# Microcontroller.net
KiCad netlist of a schematic drawn in Altium Designer
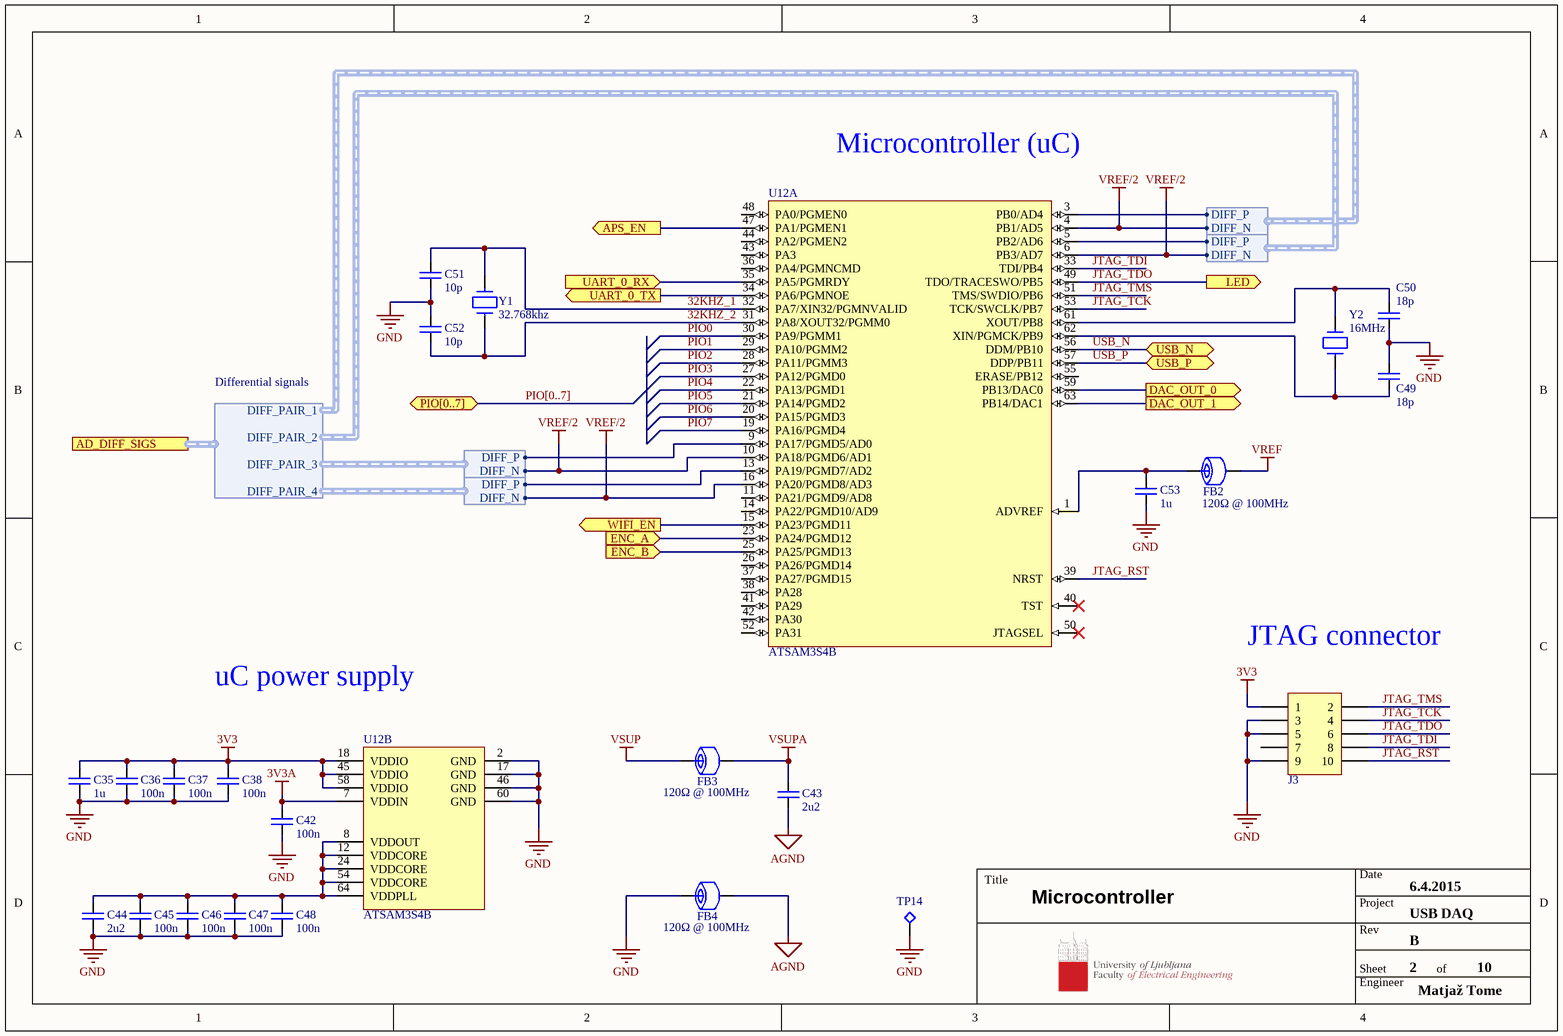
[diagram p0: Microcontroller.SchDoc]

(export (version "E")
  (design (tool "Eeschema 10.0.6"))
  (components
    (comp (ref "C35")
      (value "1u")
      (footprint "C_0603")
      (description "Generic capacitor")
      (fields (field (name "Comment") "comment"))
      (libsource (lib "DAQ") (part "Capacitor"))
    )
    (comp (ref "C36")
      (value "100n")
      (footprint "C_0603")
      (description "Generic capacitor")
      (fields (field (name "Comment") "comment"))
      (libsource (lib "DAQ") (part "Capacitor"))
    )
    (comp (ref "C37")
      (value "100n")
      (footprint "C_0603")
      (description "Generic capacitor")
      (fields (field (name "Comment") "comment"))
      (libsource (lib "DAQ") (part "Capacitor"))
    )
    (comp (ref "C38")
      (value "100n")
      (footprint "C_0603")
      (description "Generic capacitor")
      (fields (field (name "Comment") "comment"))
      (libsource (lib "DAQ") (part "Capacitor"))
    )
    (comp (ref "C42")
      (value "100n")
      (footprint "C_0603")
      (description "Generic capacitor")
      (fields (field (name "Comment") "comment"))
      (libsource (lib "DAQ") (part "Capacitor"))
    )
    (comp (ref "C43")
      (value "2u2")
      (footprint "C_0603")
      (description "Generic capacitor")
      (fields (field (name "Comment") "comment"))
      (libsource (lib "DAQ") (part "Capacitor"))
    )
    (comp (ref "C44")
      (value "2u2")
      (footprint "C_0603")
      (description "Generic capacitor")
      (fields (field (name "Comment") "comment"))
      (libsource (lib "DAQ") (part "Capacitor"))
    )
    (comp (ref "C45")
      (value "100n")
      (footprint "C_0603")
      (description "Generic capacitor")
      (fields (field (name "Comment") "comment"))
      (libsource (lib "DAQ") (part "Capacitor"))
    )
    (comp (ref "C46")
      (value "100n")
      (footprint "C_0603")
      (description "Generic capacitor")
      (fields (field (name "Comment") "comment"))
      (libsource (lib "DAQ") (part "Capacitor"))
    )
    (comp (ref "C47")
      (value "100n")
      (footprint "C_0603")
      (description "Generic capacitor")
      (fields (field (name "Comment") "comment"))
      (libsource (lib "DAQ") (part "Capacitor"))
    )
    (comp (ref "C48")
      (value "100n")
      (footprint "C_0603")
      (description "Generic capacitor")
      (fields (field (name "Comment") "comment"))
      (libsource (lib "DAQ") (part "Capacitor"))
    )
    (comp (ref "C49")
      (value "18p")
      (footprint "C_0603")
      (description "Generic capacitor")
      (fields (field (name "Comment") "comment"))
      (libsource (lib "DAQ") (part "Capacitor"))
    )
    (comp (ref "C50")
      (value "18p")
      (footprint "C_0603")
      (description "Generic capacitor")
      (fields (field (name "Comment") "comment"))
      (libsource (lib "DAQ") (part "Capacitor"))
    )
    (comp (ref "C51")
      (value "10p")
      (footprint "C_0603")
      (description "Generic capacitor")
      (fields (field (name "Comment") "comment"))
      (libsource (lib "DAQ") (part "Capacitor"))
    )
    (comp (ref "C52")
      (value "10p")
      (footprint "C_0603")
      (description "Generic capacitor")
      (fields (field (name "Comment") "comment"))
      (libsource (lib "DAQ") (part "Capacitor"))
    )
    (comp (ref "C53")
      (value "1u")
      (footprint "C_0603")
      (description "Generic capacitor")
      (fields (field (name "Comment") "comment"))
      (libsource (lib "DAQ") (part "Capacitor"))
    )
    (comp (ref "FB2")
      (value "120Ω @ 100MHz")
      (footprint "SMD_0805")
      (description "Ferrite Bead, 0805 [2012 Metric], 120 ohm, 800 mA, BLM21A Series, 0.15 ohm, ± 25%")
      (fields (field (name "MANUFACTURER") "Murata"))
      (libsource (lib "DAQ") (part "BLM21AG121SN1D"))
    )
    (comp (ref "FB3")
      (value "120Ω @ 100MHz")
      (footprint "SMD_0805")
      (description "Ferrite Bead, 0805 [2012 Metric], 120 ohm, 800 mA, BLM21A Series, 0.15 ohm, ± 25%")
      (fields (field (name "MANUFACTURER") "Murata"))
      (libsource (lib "DAQ") (part "BLM21AG121SN1D"))
    )
    (comp (ref "FB4")
      (value "120Ω @ 100MHz")
      (footprint "SMD_0805")
      (description "Ferrite Bead, 0805 [2012 Metric], 120 ohm, 800 mA, BLM21A Series, 0.15 ohm, ± 25%")
      (fields (field (name "MANUFACTURER") "Murata"))
      (libsource (lib "DAQ") (part "BLM21AG121SN1D"))
    )
    (comp (ref "J3")
      (value "M50-3600542")
      (footprint "HEADER_2X05_1.27mm")
      (description "Pin Header, Board-to-Board, 1.27 mm, 2 Rows, 10 Contacts, Surface Mount, Archer M50 Series")
      (fields (field (name "MANUFACTURER") "Harwin"))
      (libsource (lib "DAQ") (part "M50-3600542"))
    )
    (comp (ref "TP14")
      (value "testpoint")
      (footprint "TP1_FULL")
      (description "testpoint 1.5mm diameter no hole")
      (fields (field (name "PART NUMBER") "XXC0006"))
      (libsource (lib "DAQ") (part "Test Point"))
    )
    (comp (ref "U12")
      (value "ATSAM3S4B")
      (footprint "LQFP64")
      (description "Cortex M3 ARM microcontroller")
      (fields (field (name "PART NUMBER") "XAM0003") (field (name "MANUFACTURER") "Atmel"))
      (libsource (lib "DAQ") (part "ATSAM3SXB"))
    )
    (comp (ref "Y1")
      (value "32.768khz")
      (footprint "2X6_FLAT")
      (description "Crystal, 32.768 kHz, Cylinder Radial, 6.2mm x 2mm Dia, 12.5 pF, 20 ppm, R26 Series")
      (fields (field (name "PART NUMBER") "XCR0010") (field (name "MANUFACTURER") "RALTRON"))
      (libsource (lib "DAQ") (part "R26-32.768- 12.5"))
    )
    (comp (ref "Y2")
      (value "16MHz")
      (footprint "5X3.2")
      (description "Crystal, 16 MHz, SMD, 5mm x 3.2mm, 30 ppm, 18 pF, 30 ppm, 7A Series")
      (fields (field (name "MANUFACTURER") "TCX"))
      (libsource (lib "DAQ") (part "7A-16.000MAAJ-T"))
    )
  )
  (nets
    (net (code "5") (name "/32KHZ_1") (class "Default")
      (node (ref "C51") (pin "1") (pinfunction "1_1") (pintype "passive"))
      (node (ref "U12") (pin "32") (pinfunction "PA7/XIN32/PGMNVALID_32") (pintype "bidirectional"))
      (node (ref "Y1") (pin "2") (pinfunction "2_2") (pintype "passive"))
    )
    (net (code "6") (name "/32KHZ_2") (class "Default")
      (node (ref "C52") (pin "1") (pinfunction "1_1") (pintype "passive"))
      (node (ref "U12") (pin "31") (pinfunction "PA8/XOUT32/PGMM0_31") (pintype "bidirectional"))
      (node (ref "Y1") (pin "1") (pinfunction "1_1") (pintype "passive"))
    )
    (net (code "8") (name "/APS_EN") (class "Default")
      (node (ref "U12") (pin "47") (pinfunction "PA1/PGMEN1_47") (pintype "bidirectional"))
    )
    (net (code "9") (name "/DAC_OUT_0") (class "Default")
      (node (ref "U12") (pin "59") (pinfunction "PB13/DAC0_59") (pintype "bidirectional"))
    )
    (net (code "10") (name "/DAC_OUT_1") (class "Default")
      (node (ref "U12") (pin "63") (pinfunction "PB14/DAC1_63") (pintype "bidirectional"))
    )
    (net (code "11") (name "/ENC_A") (class "Default")
      (node (ref "U12") (pin "23") (pinfunction "PA24/PGMD12_23") (pintype "bidirectional"))
    )
    (net (code "12") (name "/ENC_B") (class "Default")
      (node (ref "U12") (pin "25") (pinfunction "PA25/PGMD13_25") (pintype "bidirectional"))
    )
    (net (code "13") (name "/JTAG_RST") (class "Default")
      (node (ref "J3") (pin "10") (pinfunction "10_10") (pintype "passive"))
      (node (ref "U12") (pin "39") (pinfunction "NRST_39") (pintype "bidirectional"))
    )
    (net (code "14") (name "/JTAG_TCK") (class "Default")
      (node (ref "J3") (pin "4") (pinfunction "4_4") (pintype "passive"))
      (node (ref "U12") (pin "53") (pinfunction "TCK/SWCLK/PB7_53") (pintype "bidirectional"))
    )
    (net (code "15") (name "/JTAG_TDI") (class "Default")
      (node (ref "J3") (pin "8") (pinfunction "8_8") (pintype "passive"))
      (node (ref "U12") (pin "33") (pinfunction "TDI/PB4_33") (pintype "bidirectional"))
    )
    (net (code "16") (name "/JTAG_TDO") (class "Default")
      (node (ref "J3") (pin "6") (pinfunction "6_6") (pintype "passive"))
      (node (ref "U12") (pin "49") (pinfunction "TDO/TRACESWO/PB5_49") (pintype "bidirectional"))
    )
    (net (code "17") (name "/JTAG_TMS") (class "Default")
      (node (ref "J3") (pin "2") (pinfunction "2_2") (pintype "passive"))
      (node (ref "U12") (pin "51") (pinfunction "TMS/SWDIO/PB6_51") (pintype "bidirectional"))
    )
    (net (code "18") (name "/PIO0") (class "Default")
      (node (ref "U12") (pin "30") (pinfunction "PA9/PGMM1_30") (pintype "bidirectional"))
    )
    (net (code "19") (name "/PIO1") (class "Default")
      (node (ref "U12") (pin "29") (pinfunction "PA10/PGMM2_29") (pintype "bidirectional"))
    )
    (net (code "20") (name "/PIO2") (class "Default")
      (node (ref "U12") (pin "28") (pinfunction "PA11/PGMM3_28") (pintype "bidirectional"))
    )
    (net (code "21") (name "/PIO3") (class "Default")
      (node (ref "U12") (pin "27") (pinfunction "PA12/PGMD0_27") (pintype "bidirectional"))
    )
    (net (code "22") (name "/PIO4") (class "Default")
      (node (ref "U12") (pin "22") (pinfunction "PA13/PGMD1_22") (pintype "bidirectional"))
    )
    (net (code "23") (name "/PIO5") (class "Default")
      (node (ref "U12") (pin "21") (pinfunction "PA14/PGMD2_21") (pintype "bidirectional"))
    )
    (net (code "24") (name "/PIO6") (class "Default")
      (node (ref "U12") (pin "20") (pinfunction "PA15/PGMD3_20") (pintype "bidirectional"))
    )
    (net (code "25") (name "/PIO7") (class "Default")
      (node (ref "U12") (pin "19") (pinfunction "PA16/PGMD4_19") (pintype "bidirectional"))
    )
    (net (code "27") (name "/UART_0_RX") (class "Default")
      (node (ref "U12") (pin "35") (pinfunction "PA5/PGMRDY_35") (pintype "bidirectional"))
    )
    (net (code "28") (name "/UART_0_TX") (class "Default")
      (node (ref "U12") (pin "34") (pinfunction "PA6/PGMNOE_34") (pintype "bidirectional"))
    )
    (net (code "29") (name "/USB_N") (class "Default")
      (node (ref "U12") (pin "56") (pinfunction "DDM/PB10_56") (pintype "bidirectional"))
    )
    (net (code "30") (name "/USB_P") (class "Default")
      (node (ref "U12") (pin "57") (pinfunction "DDP/PB11_57") (pintype "bidirectional"))
    )
    (net (code "31") (name "/WIFI_EN") (class "Default")
      (node (ref "U12") (pin "15") (pinfunction "PA23/PGMD11_15") (pintype "bidirectional"))
    )
    (net (code "33") (name "3V3") (class "Default")
      (node (ref "C35") (pin "1") (pinfunction "1_1") (pintype "passive"))
      (node (ref "C36") (pin "1") (pinfunction "1_1") (pintype "passive"))
      (node (ref "C37") (pin "1") (pinfunction "1_1") (pintype "passive"))
      (node (ref "C38") (pin "1") (pinfunction "1_1") (pintype "passive"))
      (node (ref "J3") (pin "1") (pinfunction "1_1") (pintype "passive"))
      (node (ref "U12") (pin "18") (pinfunction "VDDIO_18") (pintype "power_in"))
      (node (ref "U12") (pin "45") (pinfunction "VDDIO_45") (pintype "power_in"))
      (node (ref "U12") (pin "58") (pinfunction "VDDIO_58") (pintype "power_in"))
    )
    (net (code "34") (name "3V3A") (class "Default")
      (node (ref "C42") (pin "1") (pinfunction "1_1") (pintype "passive"))
      (node (ref "U12") (pin "7") (pinfunction "VDDIN_7") (pintype "power_in"))
    )
    (net (code "35") (name "AGND") (class "Default")
      (node (ref "C43") (pin "2") (pinfunction "2_2") (pintype "passive"))
      (node (ref "FB4") (pin "2") (pintype "passive"))
    )
    (net (code "36") (name "GND") (class "Default")
      (node (ref "C35") (pin "2") (pinfunction "2_2") (pintype "passive"))
      (node (ref "C36") (pin "2") (pinfunction "2_2") (pintype "passive"))
      (node (ref "C37") (pin "2") (pinfunction "2_2") (pintype "passive"))
      (node (ref "C38") (pin "2") (pinfunction "2_2") (pintype "passive"))
      (node (ref "C42") (pin "2") (pinfunction "2_2") (pintype "passive"))
      (node (ref "C44") (pin "2") (pinfunction "2_2") (pintype "passive"))
      (node (ref "C45") (pin "2") (pinfunction "2_2") (pintype "passive"))
      (node (ref "C46") (pin "2") (pinfunction "2_2") (pintype "passive"))
      (node (ref "C47") (pin "2") (pinfunction "2_2") (pintype "passive"))
      (node (ref "C48") (pin "2") (pinfunction "2_2") (pintype "passive"))
      (node (ref "C49") (pin "2") (pinfunction "2_2") (pintype "passive"))
      (node (ref "C50") (pin "2") (pinfunction "2_2") (pintype "passive"))
      (node (ref "C51") (pin "2") (pinfunction "2_2") (pintype "passive"))
      (node (ref "C52") (pin "2") (pinfunction "2_2") (pintype "passive"))
      (node (ref "C53") (pin "2") (pinfunction "2_2") (pintype "passive"))
      (node (ref "FB4") (pin "1") (pintype "passive"))
      (node (ref "J3") (pin "3") (pinfunction "3_3") (pintype "passive"))
      (node (ref "J3") (pin "5") (pinfunction "5_5") (pintype "passive"))
      (node (ref "J3") (pin "9") (pinfunction "9_9") (pintype "passive"))
      (node (ref "TP14") (pin "1") (pinfunction "1_1") (pintype "passive"))
      (node (ref "U12") (pin "17") (pinfunction "GND_17") (pintype "power_in"))
      (node (ref "U12") (pin "2") (pinfunction "GND_2") (pintype "power_in"))
      (node (ref "U12") (pin "46") (pinfunction "GND_46") (pintype "power_in"))
      (node (ref "U12") (pin "60") (pinfunction "GND_60") (pintype "power_in"))
    )
    (net (code "37") (name "Net-(U12A-ADVREF)") (class "Default")
      (node (ref "C53") (pin "1") (pinfunction "1_1") (pintype "passive"))
      (node (ref "FB2") (pin "1") (pintype "passive"))
      (node (ref "U12") (pin "1") (pinfunction "ADVREF_1") (pintype "input"))
    )
    (net (code "38") (name "Net-(U12A-XIN{slash}PGMCK{slash}PB9)") (class "Default")
      (node (ref "C49") (pin "1") (pinfunction "1_1") (pintype "passive"))
      (node (ref "U12") (pin "62") (pinfunction "XIN/PGMCK/PB9_62") (pintype "bidirectional"))
      (node (ref "Y2") (pin "1") (pinfunction "1_1") (pintype "passive"))
    )
    (net (code "39") (name "Net-(U12A-XOUT{slash}PB8)") (class "Default")
      (node (ref "C50") (pin "1") (pinfunction "1_1") (pintype "passive"))
      (node (ref "U12") (pin "61") (pinfunction "XOUT/PB8_61") (pintype "bidirectional"))
      (node (ref "Y2") (pin "2") (pinfunction "2_2") (pintype "passive"))
    )
    (net (code "40") (name "Net-(U12B-VDDOUT)") (class "Default")
      (node (ref "C44") (pin "1") (pinfunction "1_1") (pintype "passive"))
      (node (ref "C45") (pin "1") (pinfunction "1_1") (pintype "passive"))
      (node (ref "C46") (pin "1") (pinfunction "1_1") (pintype "passive"))
      (node (ref "C47") (pin "1") (pinfunction "1_1") (pintype "passive"))
      (node (ref "C48") (pin "1") (pinfunction "1_1") (pintype "passive"))
      (node (ref "U12") (pin "12") (pinfunction "VDDCORE_12") (pintype "power_in"))
      (node (ref "U12") (pin "24") (pinfunction "VDDCORE_24") (pintype "power_in"))
      (node (ref "U12") (pin "54") (pinfunction "VDDCORE_54") (pintype "power_in"))
      (node (ref "U12") (pin "64") (pinfunction "VDDPLL_64") (pintype "power_in"))
      (node (ref "U12") (pin "8") (pinfunction "VDDOUT_8") (pintype "power_in"))
    )
    (net (code "41") (name "VREF") (class "Default") (node (ref "FB2") (pin "2") (pintype "passive")))
    (net (code "42") (name "VREF{slash}2") (class "Default")
      (node (ref "U12") (pin "10") (pinfunction "PA18/PGMD6/AD1_10") (pintype "bidirectional"))
      (node (ref "U12") (pin "16") (pinfunction "PA20/PGMD8/AD3_16") (pintype "bidirectional"))
      (node (ref "U12") (pin "4") (pinfunction "PB1/AD5_4") (pintype "bidirectional"))
      (node (ref "U12") (pin "6") (pinfunction "PB3/AD7_6") (pintype "bidirectional"))
    )
    (net (code "43") (name "VSUP") (class "Default") (node (ref "FB3") (pin "1") (pintype "passive")))
    (net (code "44") (name "VSUPA") (class "Default")
      (node (ref "C43") (pin "1") (pinfunction "1_1") (pintype "passive"))
      (node (ref "FB3") (pin "2") (pintype "passive"))
    )
    (net (code "45") (name "unconnected-(J3-Pad7)") (class "Default")
      (node (ref "J3") (pin "7") (pinfunction "7_7") (pintype "passive"))
    )
    (net (code "46") (name "unconnected-(U12A-ERASE{slash}PB12-Pad55)") (class "Default")
      (node (ref "U12") (pin "55") (pinfunction "ERASE/PB12_55") (pintype "bidirectional"))
    )
    (net (code "47") (name "unconnected-(U12A-JTAGSEL-Pad50)") (class "Default")
      (node (ref "U12") (pin "50") (pinfunction "JTAGSEL_50") (pintype "input+no_connect"))
    )
    (net (code "48") (name "unconnected-(U12A-PA0{slash}PGMEN0-Pad48)") (class "Default")
      (node (ref "U12") (pin "48") (pinfunction "PA0/PGMEN0_48") (pintype "bidirectional"))
    )
    (net (code "49") (name "unconnected-(U12A-PA2{slash}PGMEN2-Pad44)") (class "Default")
      (node (ref "U12") (pin "44") (pinfunction "PA2/PGMEN2_44") (pintype "bidirectional"))
    )
    (net (code "50") (name "unconnected-(U12A-PA3-Pad43)") (class "Default")
      (node (ref "U12") (pin "43") (pinfunction "PA3_43") (pintype "bidirectional"))
    )
    (net (code "51") (name "unconnected-(U12A-PA4{slash}PGMNCMD-Pad36)") (class "Default")
      (node (ref "U12") (pin "36") (pinfunction "PA4/PGMNCMD_36") (pintype "bidirectional"))
    )
    (net (code "52") (name "unconnected-(U12A-PA17{slash}PGMD5{slash}AD0-Pad9)") (class "Default")
      (node (ref "U12") (pin "9") (pinfunction "PA17/PGMD5/AD0_9") (pintype "bidirectional"))
    )
    (net (code "53") (name "unconnected-(U12A-PA19{slash}PGMD7{slash}AD2-Pad13)") (class "Default")
      (node (ref "U12") (pin "13") (pinfunction "PA19/PGMD7/AD2_13") (pintype "bidirectional"))
    )
    (net (code "54") (name "unconnected-(U12A-PA21{slash}PGMD9{slash}AD8-Pad11)") (class "Default")
      (node (ref "U12") (pin "11") (pinfunction "PA21/PGMD9/AD8_11") (pintype "bidirectional"))
    )
    (net (code "55") (name "unconnected-(U12A-PA22{slash}PGMD10{slash}AD9-Pad14)") (class "Default")
      (node (ref "U12") (pin "14") (pinfunction "PA22/PGMD10/AD9_14") (pintype "bidirectional"))
    )
    (net (code "56") (name "unconnected-(U12A-PA26{slash}PGMD14-Pad26)") (class "Default")
      (node (ref "U12") (pin "26") (pinfunction "PA26/PGMD14_26") (pintype "bidirectional"))
    )
    (net (code "57") (name "unconnected-(U12A-PA27{slash}PGMD15-Pad37)") (class "Default")
      (node (ref "U12") (pin "37") (pinfunction "PA27/PGMD15_37") (pintype "bidirectional"))
    )
    (net (code "58") (name "unconnected-(U12A-PA28-Pad38)") (class "Default")
      (node (ref "U12") (pin "38") (pinfunction "PA28_38") (pintype "bidirectional"))
    )
    (net (code "59") (name "unconnected-(U12A-PA29-Pad41)") (class "Default")
      (node (ref "U12") (pin "41") (pinfunction "PA29_41") (pintype "bidirectional"))
    )
    (net (code "60") (name "unconnected-(U12A-PA30-Pad42)") (class "Default")
      (node (ref "U12") (pin "42") (pinfunction "PA30_42") (pintype "bidirectional"))
    )
    (net (code "61") (name "unconnected-(U12A-PA31-Pad52)") (class "Default")
      (node (ref "U12") (pin "52") (pinfunction "PA31_52") (pintype "bidirectional"))
    )
    (net (code "62") (name "unconnected-(U12A-PB0{slash}AD4-Pad3)") (class "Default")
      (node (ref "U12") (pin "3") (pinfunction "PB0/AD4_3") (pintype "bidirectional"))
    )
    (net (code "63") (name "unconnected-(U12A-PB2{slash}AD6-Pad5)") (class "Default")
      (node (ref "U12") (pin "5") (pinfunction "PB2/AD6_5") (pintype "bidirectional"))
    )
    (net (code "64") (name "unconnected-(U12A-TST-Pad40)") (class "Default")
      (node (ref "U12") (pin "40") (pinfunction "TST_40") (pintype "input+no_connect"))
    )
  )
)
